# Monotith-Small_Battery_6_0.net
KiCad netlist of a schematic drawn in Altium Designer
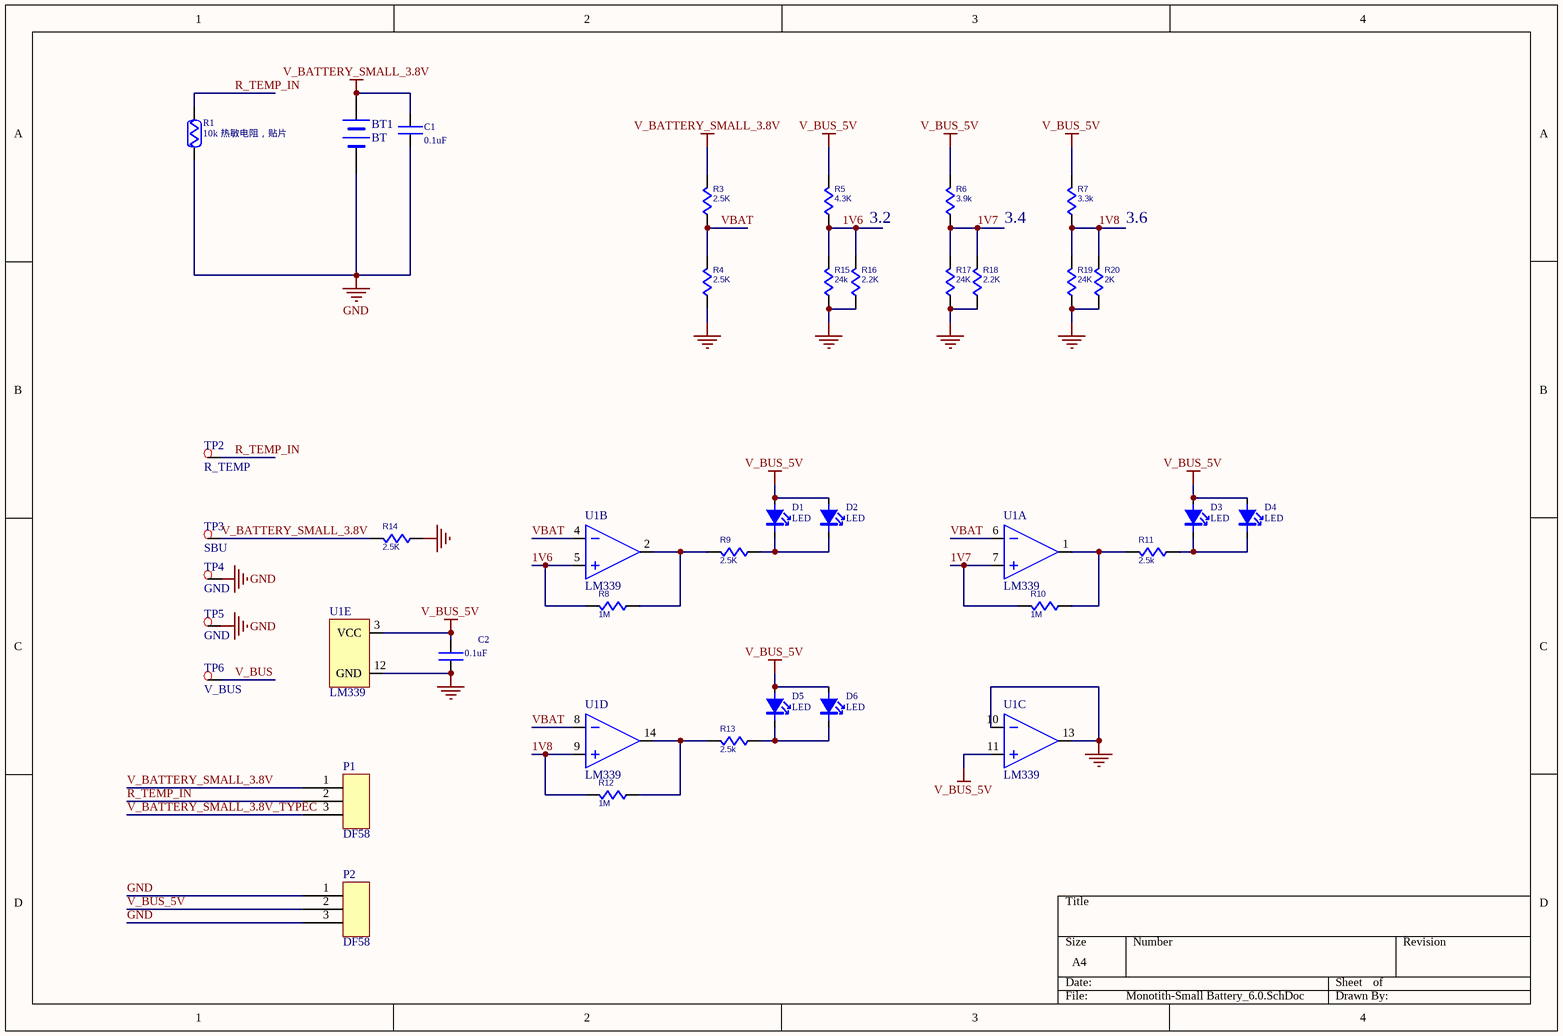
[diagram p0: Monotith-Small Battery_6.0.SchDoc]

(export (version "E")
  (design (tool "Eeschema 10.0.6"))
  (components
    (comp (ref "BT1")
      (value "BT")
      (footprint "SIP1 - 0.5")
      (description "Battery")
      (libsource (lib "*") (part "BT"))
    )
    (comp (ref "C1")
      (value "0.1uF")
      (footprint "C0402")
      (description "50V")
      (fields (field (name "TOLERANCE") "20%"))
      (libsource (lib "Project of Monolith") (part "CAP"))
    )
    (comp (ref "C2")
      (value "0.1uF")
      (footprint "C0402")
      (description "50V")
      (fields (field (name "TOLERANCE") "20%"))
      (libsource (lib "Project of Monolith") (part "CAP"))
    )
    (comp (ref "D1") (value "LED") (footprint "LED0402") (libsource (lib "Project of Monolith") (part "LED")))
    (comp (ref "D2") (value "LED") (footprint "LED0402") (libsource (lib "Project of Monolith") (part "LED")))
    (comp (ref "D3") (value "LED") (footprint "LED0402") (libsource (lib "Project of Monolith") (part "LED")))
    (comp (ref "D4") (value "LED") (footprint "LED0402") (libsource (lib "Project of Monolith") (part "LED")))
    (comp (ref "D5") (value "LED") (footprint "LED0402") (libsource (lib "Project of Monolith") (part "LED")))
    (comp (ref "D6") (value "LED") (footprint "LED0402") (libsource (lib "Project of Monolith") (part "LED")))
    (comp (ref "P1") (value "DF58") (footprint "DF58-3P") (libsource (lib "HEXCAL_SCH_LIB") (part "DF58")))
    (comp (ref "P2") (value "DF58") (footprint "DF58-3P") (libsource (lib "HEXCAL_SCH_LIB") (part "DF58")))
    (comp (ref "R1")
      (value "10k 热敏电阻，贴片")
      (footprint "HEXCAL_PCB_LIB:NTC 0402")
      (description "Resistor")
      (fields (field (name "TOLERANCE") "5%"))
      (libsource (lib "Project of Monolith") (part "NTC"))
    )
    (comp (ref "R3")
      (value "2.5K")
      (description "Resistor")
      (libsource (lib "HEXCAL_SCH_LIB") (part "RESISTOR"))
    )
    (comp (ref "R4")
      (value "2.5K")
      (description "Resistor")
      (libsource (lib "HEXCAL_SCH_LIB") (part "RESISTOR"))
    )
    (comp (ref "R5")
      (value "4.3K")
      (description "Resistor")
      (libsource (lib "HEXCAL_SCH_LIB") (part "RESISTOR"))
    )
    (comp (ref "R6")
      (value "3.9k")
      (description "Resistor")
      (libsource (lib "HEXCAL_SCH_LIB") (part "RESISTOR"))
    )
    (comp (ref "R7")
      (value "3.3k")
      (description "Resistor")
      (libsource (lib "HEXCAL_SCH_LIB") (part "RESISTOR"))
    )
    (comp (ref "R8")
      (value "1M")
      (description "Resistor")
      (libsource (lib "HEXCAL_SCH_LIB") (part "RESISTOR"))
    )
    (comp (ref "R9")
      (value "2.5K")
      (description "Resistor")
      (libsource (lib "HEXCAL_SCH_LIB") (part "RESISTOR"))
    )
    (comp (ref "R10")
      (value "1M")
      (description "Resistor")
      (libsource (lib "HEXCAL_SCH_LIB") (part "RESISTOR"))
    )
    (comp (ref "R11")
      (value "2.5k")
      (description "Resistor")
      (libsource (lib "HEXCAL_SCH_LIB") (part "RESISTOR"))
    )
    (comp (ref "R12")
      (value "1M")
      (description "Resistor")
      (libsource (lib "HEXCAL_SCH_LIB") (part "RESISTOR"))
    )
    (comp (ref "R13")
      (value "2.5k")
      (description "Resistor")
      (libsource (lib "HEXCAL_SCH_LIB") (part "RESISTOR"))
    )
    (comp (ref "R14")
      (value "2.5K")
      (description "Resistor")
      (libsource (lib "HEXCAL_SCH_LIB") (part "RESISTOR"))
    )
    (comp (ref "R15")
      (value "24k")
      (description "Resistor")
      (libsource (lib "HEXCAL_SCH_LIB") (part "RESISTOR"))
    )
    (comp (ref "R16")
      (value "2.2K")
      (description "Resistor")
      (libsource (lib "HEXCAL_SCH_LIB") (part "RESISTOR"))
    )
    (comp (ref "R17")
      (value "24K")
      (description "Resistor")
      (libsource (lib "HEXCAL_SCH_LIB") (part "RESISTOR"))
    )
    (comp (ref "R18")
      (value "2.2K")
      (description "Resistor")
      (libsource (lib "HEXCAL_SCH_LIB") (part "RESISTOR"))
    )
    (comp (ref "R19")
      (value "24K")
      (description "Resistor")
      (libsource (lib "HEXCAL_SCH_LIB") (part "RESISTOR"))
    )
    (comp (ref "R20")
      (value "2K")
      (description "Resistor")
      (libsource (lib "HEXCAL_SCH_LIB") (part "RESISTOR"))
    )
    (comp (ref "TP2")
      (value "R_TEMP")
      (footprint "HEXCAL_PCB_LIB:SIP1 - 0.5")
      (description "Testpoint")
      (libsource (lib "Project of Monolith") (part "Testpoint"))
    )
    (comp (ref "TP3")
      (value "SBU")
      (footprint "HEXCAL_PCB_LIB:SIP1 - 0.5")
      (description "Testpoint")
      (libsource (lib "Project of Monolith") (part "Testpoint"))
    )
    (comp (ref "TP4")
      (value "GND")
      (footprint "HEXCAL_PCB_LIB:SIP1 - 0.5")
      (description "Testpoint")
      (libsource (lib "Project of Monolith") (part "Testpoint"))
    )
    (comp (ref "TP5")
      (value "GND")
      (footprint "HEXCAL_PCB_LIB:SIP1 - 0.5")
      (description "Testpoint")
      (libsource (lib "HEXCAL_SCH_LIB") (part "Testpoint"))
    )
    (comp (ref "TP6")
      (value "V_BUS")
      (footprint "HEXCAL_PCB_LIB:SIP1 - 0.5")
      (description "Testpoint")
      (libsource (lib "HEXCAL_SCH_LIB") (part "Testpoint"))
    )
    (comp (ref "U1")
      (value "LM339")
      (footprint "TSOP65P640X120-14N")
      (libsource (lib "Project of Monolith") (part "LM339"))
    )
  )
  (nets
    (net (code "1") (name "/1V6") (class "Default")
      (node (ref "R15") (pin "1") (pinfunction "1_1") (pintype "passive"))
      (node (ref "R16") (pin "1") (pinfunction "1_1") (pintype "passive"))
      (node (ref "R5") (pin "2") (pinfunction "2_2") (pintype "passive"))
      (node (ref "R8") (pin "1") (pinfunction "1_1") (pintype "passive"))
      (node (ref "U1") (pin "5") (pinfunction "IN+_5") (pintype "passive"))
    )
    (net (code "2") (name "/1V7") (class "Default")
      (node (ref "R10") (pin "1") (pinfunction "1_1") (pintype "passive"))
      (node (ref "R17") (pin "1") (pinfunction "1_1") (pintype "passive"))
      (node (ref "R18") (pin "1") (pinfunction "1_1") (pintype "passive"))
      (node (ref "R6") (pin "2") (pinfunction "2_2") (pintype "passive"))
      (node (ref "U1") (pin "7") (pinfunction "IN+_7") (pintype "passive"))
    )
    (net (code "3") (name "/1V8") (class "Default")
      (node (ref "R12") (pin "1") (pinfunction "1_1") (pintype "passive"))
      (node (ref "R19") (pin "1") (pinfunction "1_1") (pintype "passive"))
      (node (ref "R20") (pin "1") (pinfunction "1_1") (pintype "passive"))
      (node (ref "R7") (pin "2") (pinfunction "2_2") (pintype "passive"))
      (node (ref "U1") (pin "9") (pinfunction "IN+_9") (pintype "passive"))
    )
    (net (code "5") (name "/R_TEMP_IN") (class "Default")
      (node (ref "P1") (pin "2") (pinfunction "2_2") (pintype "passive"))
      (node (ref "R1") (pin "1") (pinfunction "1_1") (pintype "passive"))
      (node (ref "TP2") (pin "1") (pinfunction "1_1") (pintype "passive"))
    )
    (net (code "6") (name "/VBAT") (class "Default")
      (node (ref "R3") (pin "2") (pinfunction "2_2") (pintype "passive"))
      (node (ref "R4") (pin "1") (pinfunction "1_1") (pintype "passive"))
      (node (ref "U1") (pin "4") (pinfunction "IN-_4") (pintype "passive"))
      (node (ref "U1") (pin "6") (pinfunction "IN-_6") (pintype "passive"))
      (node (ref "U1") (pin "8") (pinfunction "IN-_8") (pintype "passive"))
    )
    (net (code "7") (name "/V_BATTERY_SMALL_3.8V_TYPEC") (class "Default")
      (node (ref "P1") (pin "3") (pinfunction "3_3") (pintype "passive"))
    )
    (net (code "8") (name "/V_BUS") (class "Default")
      (node (ref "TP6") (pin "1") (pinfunction "1_1") (pintype "passive"))
    )
    (net (code "9") (name "GND") (class "Default")
      (node (ref "BT1") (pin "2") (pinfunction "-_2") (pintype "passive"))
      (node (ref "C1") (pin "2") (pinfunction "2_2") (pintype "passive"))
      (node (ref "C2") (pin "2") (pinfunction "2_2") (pintype "passive"))
      (node (ref "P2") (pin "1") (pinfunction "1_1") (pintype "passive"))
      (node (ref "P2") (pin "3") (pinfunction "3_3") (pintype "passive"))
      (node (ref "R1") (pin "2") (pinfunction "2_2") (pintype "passive"))
      (node (ref "R14") (pin "2") (pinfunction "2_2") (pintype "passive"))
      (node (ref "R15") (pin "2") (pinfunction "2_2") (pintype "passive"))
      (node (ref "R16") (pin "2") (pinfunction "2_2") (pintype "passive"))
      (node (ref "R17") (pin "2") (pinfunction "2_2") (pintype "passive"))
      (node (ref "R18") (pin "2") (pinfunction "2_2") (pintype "passive"))
      (node (ref "R19") (pin "2") (pinfunction "2_2") (pintype "passive"))
      (node (ref "R20") (pin "2") (pinfunction "2_2") (pintype "passive"))
      (node (ref "R4") (pin "2") (pinfunction "2_2") (pintype "passive"))
      (node (ref "TP4") (pin "1") (pinfunction "1_1") (pintype "passive"))
      (node (ref "TP5") (pin "1") (pinfunction "1_1") (pintype "passive"))
      (node (ref "U1") (pin "10") (pinfunction "IN+_10") (pintype "passive"))
      (node (ref "U1") (pin "12") (pinfunction "GND_12") (pintype "passive"))
      (node (ref "U1") (pin "13") (pinfunction "OUT_13") (pintype "passive"))
    )
    (net (code "10") (name "Net-(D1-PadK)") (class "Default")
      (node (ref "D1") (pin "K") (pinfunction "K_K") (pintype "passive"))
      (node (ref "D2") (pin "K") (pinfunction "K_K") (pintype "passive"))
      (node (ref "R9") (pin "2") (pinfunction "2_2") (pintype "passive"))
    )
    (net (code "11") (name "Net-(D3-PadK)") (class "Default")
      (node (ref "D3") (pin "K") (pinfunction "K_K") (pintype "passive"))
      (node (ref "D4") (pin "K") (pinfunction "K_K") (pintype "passive"))
      (node (ref "R11") (pin "2") (pinfunction "2_2") (pintype "passive"))
    )
    (net (code "12") (name "Net-(D5-PadK)") (class "Default")
      (node (ref "D5") (pin "K") (pinfunction "K_K") (pintype "passive"))
      (node (ref "D6") (pin "K") (pinfunction "K_K") (pintype "passive"))
      (node (ref "R13") (pin "2") (pinfunction "2_2") (pintype "passive"))
    )
    (net (code "13") (name "Net-(U1A-OUT)") (class "Default")
      (node (ref "R10") (pin "2") (pinfunction "2_2") (pintype "passive"))
      (node (ref "R11") (pin "1") (pinfunction "1_1") (pintype "passive"))
      (node (ref "U1") (pin "1") (pinfunction "OUT_1") (pintype "passive"))
    )
    (net (code "14") (name "Net-(U1B-OUT)") (class "Default")
      (node (ref "R8") (pin "2") (pinfunction "2_2") (pintype "passive"))
      (node (ref "R9") (pin "1") (pinfunction "1_1") (pintype "passive"))
      (node (ref "U1") (pin "2") (pinfunction "OUT_2") (pintype "passive"))
    )
    (net (code "15") (name "Net-(U1D-OUT)") (class "Default")
      (node (ref "R12") (pin "2") (pinfunction "2_2") (pintype "passive"))
      (node (ref "R13") (pin "1") (pinfunction "1_1") (pintype "passive"))
      (node (ref "U1") (pin "14") (pinfunction "OUT_14") (pintype "passive"))
    )
    (net (code "16") (name "V_BATTERY_SMALL_3.8V") (class "Default")
      (node (ref "BT1") (pin "1") (pinfunction "+_1") (pintype "passive"))
      (node (ref "C1") (pin "1") (pinfunction "1_1") (pintype "passive"))
      (node (ref "P1") (pin "1") (pinfunction "1_1") (pintype "passive"))
      (node (ref "R14") (pin "1") (pinfunction "1_1") (pintype "passive"))
      (node (ref "R3") (pin "1") (pinfunction "1_1") (pintype "passive"))
      (node (ref "TP3") (pin "1") (pinfunction "1_1") (pintype "passive"))
    )
    (net (code "17") (name "V_BUS_5V") (class "Default")
      (node (ref "C2") (pin "1") (pinfunction "1_1") (pintype "passive"))
      (node (ref "D1") (pin "A") (pinfunction "A_A") (pintype "passive"))
      (node (ref "D2") (pin "A") (pinfunction "A_A") (pintype "passive"))
      (node (ref "D3") (pin "A") (pinfunction "A_A") (pintype "passive"))
      (node (ref "D4") (pin "A") (pinfunction "A_A") (pintype "passive"))
      (node (ref "D5") (pin "A") (pinfunction "A_A") (pintype "passive"))
      (node (ref "D6") (pin "A") (pinfunction "A_A") (pintype "passive"))
      (node (ref "P2") (pin "2") (pinfunction "2_2") (pintype "passive"))
      (node (ref "R5") (pin "1") (pinfunction "1_1") (pintype "passive"))
      (node (ref "R6") (pin "1") (pinfunction "1_1") (pintype "passive"))
      (node (ref "R7") (pin "1") (pinfunction "1_1") (pintype "passive"))
      (node (ref "U1") (pin "11") (pinfunction "IN-_11") (pintype "passive"))
      (node (ref "U1") (pin "3") (pinfunction "VCC_3") (pintype "passive"))
    )
  )
)
